# PortalsDualExpVCA.net
KiCad netlist of a schematic drawn in EAGLE
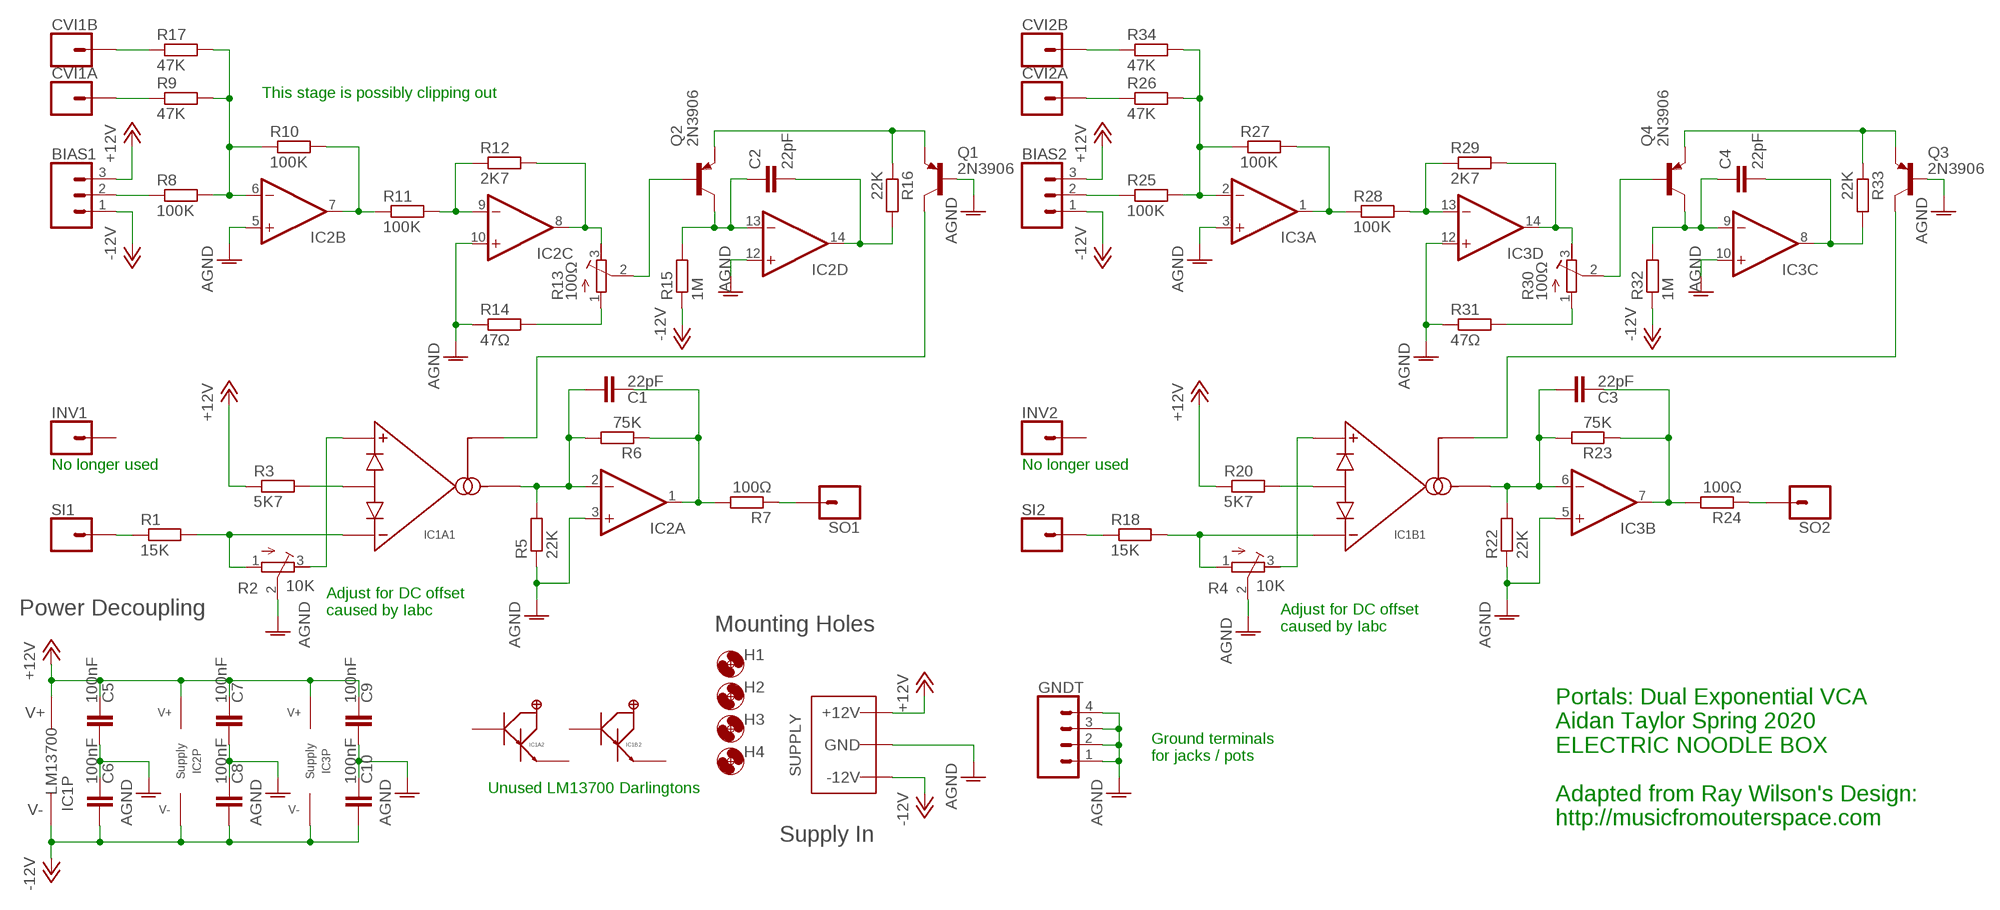
[diagram p0: schematic, sheet 1]

(export (version "E")
  (design (tool "Eeschema 10.0.6"))
  (components
    (comp (ref "BIAS1")
      (value "3XWIREPAD")
      (footprint "eagle-import:1X03")
      (libsource (lib "eagle-import") (part "3XWIREPAD"))
    )
    (comp (ref "BIAS2")
      (value "3XWIREPAD")
      (footprint "eagle-import:1X03")
      (libsource (lib "eagle-import") (part "3XWIREPAD"))
    )
    (comp (ref "C1")
      (value "22pF")
      (footprint "eagle-import:C050-025X075")
      (libsource (lib "eagle-import") (part "C-EU050-025X075"))
    )
    (comp (ref "C2")
      (value "22pF")
      (footprint "eagle-import:C050-025X075")
      (libsource (lib "eagle-import") (part "C-EU050-025X075"))
    )
    (comp (ref "C3")
      (value "22pF")
      (footprint "eagle-import:C050-025X075")
      (libsource (lib "eagle-import") (part "C-EU050-025X075"))
    )
    (comp (ref "C4")
      (value "22pF")
      (footprint "eagle-import:C050-025X075")
      (libsource (lib "eagle-import") (part "C-EU050-025X075"))
    )
    (comp (ref "C5")
      (value "100nF")
      (footprint "eagle-import:C050-025X075")
      (libsource (lib "eagle-import") (part "C-EU050-025X075"))
    )
    (comp (ref "C6")
      (value "100nF")
      (footprint "eagle-import:C050-025X075")
      (libsource (lib "eagle-import") (part "C-EU050-025X075"))
    )
    (comp (ref "C7")
      (value "100nF")
      (footprint "eagle-import:C050-025X075")
      (libsource (lib "eagle-import") (part "C-EU050-025X075"))
    )
    (comp (ref "C8")
      (value "100nF")
      (footprint "eagle-import:C050-025X075")
      (libsource (lib "eagle-import") (part "C-EU050-025X075"))
    )
    (comp (ref "C9")
      (value "100nF")
      (footprint "eagle-import:C050-025X075")
      (libsource (lib "eagle-import") (part "C-EU050-025X075"))
    )
    (comp (ref "C10")
      (value "100nF")
      (footprint "eagle-import:C050-025X075")
      (libsource (lib "eagle-import") (part "C-EU050-025X075"))
    )
    (comp (ref "CVI1A")
      (value "1XWIREPAD")
      (footprint "eagle-import:1X01")
      (libsource (lib "eagle-import") (part "1XWIREPAD"))
    )
    (comp (ref "CVI1B")
      (value "1XWIREPAD")
      (footprint "eagle-import:1X01")
      (libsource (lib "eagle-import") (part "1XWIREPAD"))
    )
    (comp (ref "CVI2A")
      (value "1XWIREPAD")
      (footprint "eagle-import:1X01")
      (libsource (lib "eagle-import") (part "1XWIREPAD"))
    )
    (comp (ref "CVI2B")
      (value "1XWIREPAD")
      (footprint "eagle-import:1X01")
      (libsource (lib "eagle-import") (part "1XWIREPAD"))
    )
    (comp (ref "GNDT")
      (value "4XWIREPAD")
      (footprint "eagle-import:1X04")
      (libsource (lib "eagle-import") (part "4XWIREPAD"))
    )
    (comp (ref "H1")
      (value "MOUNT-HOLE3.2")
      (footprint "eagle-import:3,2")
      (libsource (lib "eagle-import") (part "MOUNT-HOLE3.2"))
    )
    (comp (ref "H2")
      (value "MOUNT-HOLE3.2")
      (footprint "eagle-import:3,2")
      (libsource (lib "eagle-import") (part "MOUNT-HOLE3.2"))
    )
    (comp (ref "H3")
      (value "MOUNT-HOLE3.2")
      (footprint "eagle-import:3,2")
      (libsource (lib "eagle-import") (part "MOUNT-HOLE3.2"))
    )
    (comp (ref "H4")
      (value "MOUNT-HOLE3.2")
      (footprint "eagle-import:3,2")
      (libsource (lib "eagle-import") (part "MOUNT-HOLE3.2"))
    )
    (comp (ref "IC1")
      (value "LM13700DIL")
      (footprint "eagle-import:DIL16")
      (libsource (lib "eagle-import") (part "LM13700DIL"))
    )
    (comp (ref "IC2")
      (value "TL0X4DIL")
      (footprint "eagle-import:DIL14")
      (libsource (lib "eagle-import") (part "TL0X4DIL"))
    )
    (comp (ref "IC3")
      (value "TL0X4DIL")
      (footprint "eagle-import:DIL14")
      (libsource (lib "eagle-import") (part "TL0X4DIL"))
    )
    (comp (ref "INV1")
      (value "1XWIREPAD")
      (footprint "eagle-import:1X01")
      (libsource (lib "eagle-import") (part "1XWIREPAD"))
    )
    (comp (ref "INV2")
      (value "1XWIREPAD")
      (footprint "eagle-import:1X01")
      (libsource (lib "eagle-import") (part "1XWIREPAD"))
    )
    (comp (ref "Q1")
      (value "2N3906")
      (footprint "eagle-import:TO92")
      (libsource (lib "eagle-import") (part "2N3906"))
    )
    (comp (ref "Q2")
      (value "2N3906")
      (footprint "eagle-import:TO92")
      (libsource (lib "eagle-import") (part "2N3906"))
    )
    (comp (ref "Q3")
      (value "2N3906")
      (footprint "eagle-import:TO92")
      (libsource (lib "eagle-import") (part "2N3906"))
    )
    (comp (ref "Q4")
      (value "2N3906")
      (footprint "eagle-import:TO92")
      (libsource (lib "eagle-import") (part "2N3906"))
    )
    (comp (ref "R1")
      (value "15K")
      (footprint "eagle-import:0207_10")
      (libsource (lib "eagle-import") (part "R-EU_0207/10"))
    )
    (comp (ref "R2")
      (value "10K")
      (footprint "eagle-import:RTRIM3296W")
      (libsource (lib "eagle-import") (part "R-TRIMM3296W"))
    )
    (comp (ref "R3")
      (value "5K7")
      (footprint "eagle-import:0207_10")
      (libsource (lib "eagle-import") (part "R-EU_0207/10"))
    )
    (comp (ref "R4")
      (value "10K")
      (footprint "eagle-import:RTRIM3296W")
      (libsource (lib "eagle-import") (part "R-TRIMM3296W"))
    )
    (comp (ref "R5")
      (value "22K")
      (footprint "eagle-import:0207_10")
      (libsource (lib "eagle-import") (part "R-EU_0207/10"))
    )
    (comp (ref "R6")
      (value "75K")
      (footprint "eagle-import:0207_10")
      (libsource (lib "eagle-import") (part "R-EU_0207/10"))
    )
    (comp (ref "R7")
      (value "100Ω")
      (footprint "eagle-import:0207_10")
      (libsource (lib "eagle-import") (part "R-EU_0207/10"))
    )
    (comp (ref "R8")
      (value "100K")
      (footprint "eagle-import:0207_10")
      (libsource (lib "eagle-import") (part "R-EU_0207/10"))
    )
    (comp (ref "R9")
      (value "47K")
      (footprint "eagle-import:0207_10")
      (libsource (lib "eagle-import") (part "R-EU_0207/10"))
    )
    (comp (ref "R10")
      (value "100K")
      (footprint "eagle-import:0207_10")
      (libsource (lib "eagle-import") (part "R-EU_0207/10"))
    )
    (comp (ref "R11")
      (value "100K")
      (footprint "eagle-import:0207_10")
      (libsource (lib "eagle-import") (part "R-EU_0207/10"))
    )
    (comp (ref "R12")
      (value "2K7")
      (footprint "eagle-import:0207_10")
      (libsource (lib "eagle-import") (part "R-EU_0207/10"))
    )
    (comp (ref "R13")
      (value "100Ω")
      (footprint "eagle-import:RTRIM3296W")
      (libsource (lib "eagle-import") (part "R-TRIMM3296W"))
    )
    (comp (ref "R14")
      (value "47Ω")
      (footprint "eagle-import:0207_10")
      (libsource (lib "eagle-import") (part "R-EU_0207/10"))
    )
    (comp (ref "R15")
      (value "1M")
      (footprint "eagle-import:0207_10")
      (libsource (lib "eagle-import") (part "R-EU_0207/10"))
    )
    (comp (ref "R16")
      (value "22K")
      (footprint "eagle-import:0207_10")
      (libsource (lib "eagle-import") (part "R-EU_0207/10"))
    )
    (comp (ref "R17")
      (value "47K")
      (footprint "eagle-import:0207_10")
      (libsource (lib "eagle-import") (part "R-EU_0207/10"))
    )
    (comp (ref "R18")
      (value "15K")
      (footprint "eagle-import:0207_10")
      (libsource (lib "eagle-import") (part "R-EU_0207/10"))
    )
    (comp (ref "R20")
      (value "5K7")
      (footprint "eagle-import:0207_10")
      (libsource (lib "eagle-import") (part "R-EU_0207/10"))
    )
    (comp (ref "R22")
      (value "22K")
      (footprint "eagle-import:0207_10")
      (libsource (lib "eagle-import") (part "R-EU_0207/10"))
    )
    (comp (ref "R23")
      (value "75K")
      (footprint "eagle-import:0207_10")
      (libsource (lib "eagle-import") (part "R-EU_0207/10"))
    )
    (comp (ref "R24")
      (value "100Ω")
      (footprint "eagle-import:0207_10")
      (libsource (lib "eagle-import") (part "R-EU_0207/10"))
    )
    (comp (ref "R25")
      (value "100K")
      (footprint "eagle-import:0207_10")
      (libsource (lib "eagle-import") (part "R-EU_0207/10"))
    )
    (comp (ref "R26")
      (value "47K")
      (footprint "eagle-import:0207_10")
      (libsource (lib "eagle-import") (part "R-EU_0207/10"))
    )
    (comp (ref "R27")
      (value "100K")
      (footprint "eagle-import:0207_10")
      (libsource (lib "eagle-import") (part "R-EU_0207/10"))
    )
    (comp (ref "R28")
      (value "100K")
      (footprint "eagle-import:0207_10")
      (libsource (lib "eagle-import") (part "R-EU_0207/10"))
    )
    (comp (ref "R29")
      (value "2K7")
      (footprint "eagle-import:0207_10")
      (libsource (lib "eagle-import") (part "R-EU_0207/10"))
    )
    (comp (ref "R30")
      (value "100Ω")
      (footprint "eagle-import:RTRIM3296W")
      (libsource (lib "eagle-import") (part "R-TRIMM3296W"))
    )
    (comp (ref "R31")
      (value "47Ω")
      (footprint "eagle-import:0207_10")
      (libsource (lib "eagle-import") (part "R-EU_0207/10"))
    )
    (comp (ref "R32")
      (value "1M")
      (footprint "eagle-import:0207_10")
      (libsource (lib "eagle-import") (part "R-EU_0207/10"))
    )
    (comp (ref "R33")
      (value "22K")
      (footprint "eagle-import:0207_10")
      (libsource (lib "eagle-import") (part "R-EU_0207/10"))
    )
    (comp (ref "R34")
      (value "47K")
      (footprint "eagle-import:0207_10")
      (libsource (lib "eagle-import") (part "R-EU_0207/10"))
    )
    (comp (ref "SI1")
      (value "1XWIREPAD")
      (footprint "eagle-import:1X01")
      (libsource (lib "eagle-import") (part "1XWIREPAD"))
    )
    (comp (ref "SI2")
      (value "1XWIREPAD")
      (footprint "eagle-import:1X01")
      (libsource (lib "eagle-import") (part "1XWIREPAD"))
    )
    (comp (ref "SO1")
      (value "1XWIREPAD")
      (footprint "eagle-import:1X01")
      (libsource (lib "eagle-import") (part "1XWIREPAD"))
    )
    (comp (ref "SO2")
      (value "1XWIREPAD")
      (footprint "eagle-import:1X01")
      (libsource (lib "eagle-import") (part "1XWIREPAD"))
    )
    (comp (ref "WP1")
      (value "COMBO_SUPPLY_HEADER")
      (footprint "eagle-import:COMBINED_POWER")
      (libsource (lib "eagle-import") (part "COMBO_SUPPLY_HEADER"))
    )
  )
  (nets
    (net (code "1") (name "+12V") (class "Default")
      (node (ref "BIAS1") (pin "3") (pinfunction "3_3") (pintype "passive"))
      (node (ref "BIAS2") (pin "3") (pinfunction "3_3") (pintype "passive"))
      (node (ref "C5") (pin "2") (pinfunction "2_2") (pintype "passive"))
      (node (ref "C7") (pin "2") (pinfunction "2_2") (pintype "passive"))
      (node (ref "C9") (pin "2") (pinfunction "2_2") (pintype "passive"))
      (node (ref "IC1") (pin "11") (pinfunction "V+_11") (pintype "power_in"))
      (node (ref "IC2") (pin "4") (pinfunction "V+_4") (pintype "bidirectional"))
      (node (ref "IC3") (pin "4") (pinfunction "V+_4") (pintype "bidirectional"))
      (node (ref "R20") (pin "1") (pinfunction "1_1") (pintype "passive"))
      (node (ref "R3") (pin "1") (pinfunction "1_1") (pintype "passive"))
      (node (ref "WP1") (pin "V+1") (pinfunction "V++_V+1") (pintype "power_in"))
      (node (ref "WP1") (pin "V+2") (pinfunction "V++_V+2") (pintype "power_in"))
      (node (ref "WP1") (pin "V+3") (pinfunction "V++_V+3") (pintype "power_in"))
    )
    (net (code "2") (name "-12V") (class "Default")
      (node (ref "BIAS1") (pin "1") (pinfunction "1_1") (pintype "passive"))
      (node (ref "BIAS2") (pin "1") (pinfunction "1_1") (pintype "passive"))
      (node (ref "C10") (pin "1") (pinfunction "1_1") (pintype "passive"))
      (node (ref "C6") (pin "1") (pinfunction "1_1") (pintype "passive"))
      (node (ref "C8") (pin "1") (pinfunction "1_1") (pintype "passive"))
      (node (ref "IC1") (pin "6") (pinfunction "V-_6") (pintype "power_in"))
      (node (ref "IC2") (pin "11") (pinfunction "V-_11") (pintype "bidirectional"))
      (node (ref "IC3") (pin "11") (pinfunction "V-_11") (pintype "bidirectional"))
      (node (ref "R15") (pin "1") (pinfunction "1_1") (pintype "passive"))
      (node (ref "R32") (pin "1") (pinfunction "1_1") (pintype "passive"))
      (node (ref "WP1") (pin "V-1") (pinfunction "V--_V-1") (pintype "power_in"))
      (node (ref "WP1") (pin "V-2") (pinfunction "V--_V-2") (pintype "power_in"))
      (node (ref "WP1") (pin "V-3") (pinfunction "V--_V-3") (pintype "power_in"))
    )
    (net (code "3") (name "AGND") (class "Default")
      (node (ref "C10") (pin "2") (pinfunction "2_2") (pintype "passive"))
      (node (ref "C5") (pin "1") (pinfunction "1_1") (pintype "passive"))
      (node (ref "C6") (pin "2") (pinfunction "2_2") (pintype "passive"))
      (node (ref "C7") (pin "1") (pinfunction "1_1") (pintype "passive"))
      (node (ref "C8") (pin "2") (pinfunction "2_2") (pintype "passive"))
      (node (ref "C9") (pin "1") (pinfunction "1_1") (pintype "passive"))
      (node (ref "GNDT") (pin "1") (pinfunction "1_1") (pintype "passive"))
      (node (ref "GNDT") (pin "2") (pinfunction "2_2") (pintype "passive"))
      (node (ref "GNDT") (pin "3") (pinfunction "3_3") (pintype "passive"))
      (node (ref "GNDT") (pin "4") (pinfunction "4_4") (pintype "passive"))
      (node (ref "IC2") (pin "10") (pinfunction "+IN_10") (pintype "input"))
      (node (ref "IC2") (pin "12") (pinfunction "+IN_12") (pintype "input"))
      (node (ref "IC2") (pin "3") (pinfunction "+IN_3") (pintype "input"))
      (node (ref "IC2") (pin "5") (pinfunction "+IN_5") (pintype "input"))
      (node (ref "IC3") (pin "10") (pinfunction "+IN_10") (pintype "input"))
      (node (ref "IC3") (pin "12") (pinfunction "+IN_12") (pintype "input"))
      (node (ref "IC3") (pin "3") (pinfunction "+IN_3") (pintype "input"))
      (node (ref "IC3") (pin "5") (pinfunction "+IN_5") (pintype "input"))
      (node (ref "Q1") (pin "2") (pinfunction "B_2") (pintype "passive"))
      (node (ref "Q3") (pin "2") (pinfunction "B_2") (pintype "passive"))
      (node (ref "R14") (pin "1") (pinfunction "1_1") (pintype "passive"))
      (node (ref "R2") (pin "2") (pinfunction "S_2") (pintype "passive"))
      (node (ref "R22") (pin "1") (pinfunction "1_1") (pintype "passive"))
      (node (ref "R31") (pin "1") (pinfunction "1_1") (pintype "passive"))
      (node (ref "R4") (pin "2") (pinfunction "S_2") (pintype "passive"))
      (node (ref "R5") (pin "1") (pinfunction "1_1") (pintype "passive"))
      (node (ref "WP1") (pin "GND1") (pinfunction "AGND_GND1") (pintype "power_in"))
      (node (ref "WP1") (pin "GND2") (pinfunction "AGND_GND2") (pintype "power_in"))
      (node (ref "WP1") (pin "GND3") (pinfunction "AGND_GND3") (pintype "power_in"))
      (node (ref "WP1") (pin "GND4") (pinfunction "AGND_GND4") (pintype "power_in"))
      (node (ref "WP1") (pin "GND5") (pinfunction "AGND_GND5") (pintype "power_in"))
      (node (ref "WP1") (pin "GND6") (pinfunction "AGND_GND6") (pintype "power_in"))
      (node (ref "WP1") (pin "GND7") (pinfunction "AGND_GND7") (pintype "power_in"))
      (node (ref "WP1") (pin "GND8") (pinfunction "AGND_GND8") (pintype "power_in"))
    )
    (net (code "4") (name "Net-(BIAS1-Pad2)") (class "Default")
      (node (ref "BIAS1") (pin "2") (pinfunction "2_2") (pintype "passive"))
      (node (ref "R8") (pin "1") (pinfunction "1_1") (pintype "passive"))
    )
    (net (code "5") (name "Net-(BIAS2-Pad2)") (class "Default")
      (node (ref "BIAS2") (pin "2") (pinfunction "2_2") (pintype "passive"))
      (node (ref "R25") (pin "1") (pinfunction "1_1") (pintype "passive"))
    )
    (net (code "6") (name "Net-(CVI1A-Pad1)") (class "Default")
      (node (ref "CVI1A") (pin "1") (pinfunction "1_1") (pintype "passive"))
      (node (ref "R9") (pin "1") (pinfunction "1_1") (pintype "passive"))
    )
    (net (code "7") (name "Net-(CVI1B-Pad1)") (class "Default")
      (node (ref "CVI1B") (pin "1") (pinfunction "1_1") (pintype "passive"))
      (node (ref "R17") (pin "1") (pinfunction "1_1") (pintype "passive"))
    )
    (net (code "8") (name "Net-(CVI2A-Pad1)") (class "Default")
      (node (ref "CVI2A") (pin "1") (pinfunction "1_1") (pintype "passive"))
      (node (ref "R26") (pin "1") (pinfunction "1_1") (pintype "passive"))
    )
    (net (code "9") (name "Net-(CVI2B-Pad1)") (class "Default")
      (node (ref "CVI2B") (pin "1") (pinfunction "1_1") (pintype "passive"))
      (node (ref "R34") (pin "1") (pinfunction "1_1") (pintype "passive"))
    )
    (net (code "10") (name "Net-(IC1A-AMP+)") (class "Default")
      (node (ref "IC1") (pin "3") (pinfunction "AMP+_3") (pintype "input"))
      (node (ref "R2") (pin "3") (pinfunction "E_3") (pintype "passive"))
    )
    (net (code "11") (name "Net-(IC1A-AMP-)") (class "Default")
      (node (ref "IC1") (pin "4") (pinfunction "AMP-_4") (pintype "input"))
      (node (ref "R1") (pin "2") (pinfunction "2_2") (pintype "passive"))
      (node (ref "R2") (pin "1") (pinfunction "A_1") (pintype "passive"))
    )
    (net (code "12") (name "Net-(IC1A-AMPBIAS)") (class "Default")
      (node (ref "IC1") (pin "1") (pinfunction "AMPBIAS_1") (pintype "input"))
      (node (ref "Q1") (pin "1") (pinfunction "C_1") (pintype "passive"))
    )
    (net (code "13") (name "Net-(IC1A-AMPOUT)") (class "Default")
      (node (ref "C1") (pin "1") (pinfunction "1_1") (pintype "passive"))
      (node (ref "IC1") (pin "5") (pinfunction "AMPOUT_5") (pintype "output"))
      (node (ref "IC2") (pin "2") (pinfunction "-IN_2") (pintype "input"))
      (node (ref "R5") (pin "2") (pinfunction "2_2") (pintype "passive"))
      (node (ref "R6") (pin "2") (pinfunction "2_2") (pintype "passive"))
    )
    (net (code "14") (name "Net-(IC1A-DIODES)") (class "Default")
      (node (ref "IC1") (pin "2") (pinfunction "DIODES_2") (pintype "input"))
      (node (ref "R3") (pin "2") (pinfunction "2_2") (pintype "passive"))
    )
    (net (code "15") (name "Net-(IC1C-AMP+)") (class "Default")
      (node (ref "IC1") (pin "14") (pinfunction "AMP+_14") (pintype "input"))
      (node (ref "R4") (pin "3") (pinfunction "E_3") (pintype "passive"))
    )
    (net (code "16") (name "Net-(IC1C-AMP-)") (class "Default")
      (node (ref "IC1") (pin "13") (pinfunction "AMP-_13") (pintype "input"))
      (node (ref "R18") (pin "2") (pinfunction "2_2") (pintype "passive"))
      (node (ref "R4") (pin "1") (pinfunction "A_1") (pintype "passive"))
    )
    (net (code "17") (name "Net-(IC1C-AMPBIAS)") (class "Default")
      (node (ref "IC1") (pin "16") (pinfunction "AMPBIAS_16") (pintype "input"))
      (node (ref "Q3") (pin "1") (pinfunction "C_1") (pintype "passive"))
    )
    (net (code "18") (name "Net-(IC1C-AMPOUT)") (class "Default")
      (node (ref "C3") (pin "1") (pinfunction "1_1") (pintype "passive"))
      (node (ref "IC1") (pin "12") (pinfunction "AMPOUT_12") (pintype "output"))
      (node (ref "IC3") (pin "6") (pinfunction "-IN_6") (pintype "input"))
      (node (ref "R22") (pin "2") (pinfunction "2_2") (pintype "passive"))
      (node (ref "R23") (pin "2") (pinfunction "2_2") (pintype "passive"))
    )
    (net (code "19") (name "Net-(IC1C-DIODES)") (class "Default")
      (node (ref "IC1") (pin "15") (pinfunction "DIODES_15") (pintype "input"))
      (node (ref "R20") (pin "2") (pinfunction "2_2") (pintype "passive"))
    )
    (net (code "20") (name "Net-(IC2A-OUT)") (class "Default")
      (node (ref "C1") (pin "2") (pinfunction "2_2") (pintype "passive"))
      (node (ref "IC2") (pin "1") (pinfunction "OUT_1") (pintype "output"))
      (node (ref "R6") (pin "1") (pinfunction "1_1") (pintype "passive"))
      (node (ref "R7") (pin "2") (pinfunction "2_2") (pintype "passive"))
    )
    (net (code "21") (name "Net-(IC2B--IN)") (class "Default")
      (node (ref "IC2") (pin "6") (pinfunction "-IN_6") (pintype "input"))
      (node (ref "R10") (pin "1") (pinfunction "1_1") (pintype "passive"))
      (node (ref "R17") (pin "2") (pinfunction "2_2") (pintype "passive"))
      (node (ref "R8") (pin "2") (pinfunction "2_2") (pintype "passive"))
      (node (ref "R9") (pin "2") (pinfunction "2_2") (pintype "passive"))
    )
    (net (code "22") (name "Net-(IC2B-OUT)") (class "Default")
      (node (ref "IC2") (pin "7") (pinfunction "OUT_7") (pintype "output"))
      (node (ref "R10") (pin "2") (pinfunction "2_2") (pintype "passive"))
      (node (ref "R11") (pin "1") (pinfunction "1_1") (pintype "passive"))
    )
    (net (code "23") (name "Net-(IC2C--IN)") (class "Default")
      (node (ref "IC2") (pin "9") (pinfunction "-IN_9") (pintype "input"))
      (node (ref "R11") (pin "2") (pinfunction "2_2") (pintype "passive"))
      (node (ref "R12") (pin "1") (pinfunction "1_1") (pintype "passive"))
    )
    (net (code "24") (name "Net-(IC2C-OUT)") (class "Default")
      (node (ref "IC2") (pin "8") (pinfunction "OUT_8") (pintype "output"))
      (node (ref "R12") (pin "2") (pinfunction "2_2") (pintype "passive"))
      (node (ref "R13") (pin "3") (pinfunction "E_3") (pintype "passive"))
    )
    (net (code "25") (name "Net-(IC2D--IN)") (class "Default")
      (node (ref "C2") (pin "1") (pinfunction "1_1") (pintype "passive"))
      (node (ref "IC2") (pin "13") (pinfunction "-IN_13") (pintype "input"))
      (node (ref "Q2") (pin "1") (pinfunction "C_1") (pintype "passive"))
      (node (ref "R15") (pin "2") (pinfunction "2_2") (pintype "passive"))
    )
    (net (code "26") (name "Net-(IC2D-OUT)") (class "Default")
      (node (ref "C2") (pin "2") (pinfunction "2_2") (pintype "passive"))
      (node (ref "IC2") (pin "14") (pinfunction "OUT_14") (pintype "output"))
      (node (ref "R16") (pin "2") (pinfunction "2_2") (pintype "passive"))
    )
    (net (code "27") (name "Net-(IC3A--IN)") (class "Default")
      (node (ref "IC3") (pin "2") (pinfunction "-IN_2") (pintype "input"))
      (node (ref "R25") (pin "2") (pinfunction "2_2") (pintype "passive"))
      (node (ref "R26") (pin "2") (pinfunction "2_2") (pintype "passive"))
      (node (ref "R27") (pin "1") (pinfunction "1_1") (pintype "passive"))
      (node (ref "R34") (pin "2") (pinfunction "2_2") (pintype "passive"))
    )
    (net (code "28") (name "Net-(IC3A-OUT)") (class "Default")
      (node (ref "IC3") (pin "1") (pinfunction "OUT_1") (pintype "output"))
      (node (ref "R27") (pin "2") (pinfunction "2_2") (pintype "passive"))
      (node (ref "R28") (pin "1") (pinfunction "1_1") (pintype "passive"))
    )
    (net (code "29") (name "Net-(IC3B-OUT)") (class "Default")
      (node (ref "C3") (pin "2") (pinfunction "2_2") (pintype "passive"))
      (node (ref "IC3") (pin "7") (pinfunction "OUT_7") (pintype "output"))
      (node (ref "R23") (pin "1") (pinfunction "1_1") (pintype "passive"))
      (node (ref "R24") (pin "2") (pinfunction "2_2") (pintype "passive"))
    )
    (net (code "30") (name "Net-(IC3C--IN)") (class "Default")
      (node (ref "C4") (pin "1") (pinfunction "1_1") (pintype "passive"))
      (node (ref "IC3") (pin "9") (pinfunction "-IN_9") (pintype "input"))
      (node (ref "Q4") (pin "1") (pinfunction "C_1") (pintype "passive"))
      (node (ref "R32") (pin "2") (pinfunction "2_2") (pintype "passive"))
    )
    (net (code "31") (name "Net-(IC3C-OUT)") (class "Default")
      (node (ref "C4") (pin "2") (pinfunction "2_2") (pintype "passive"))
      (node (ref "IC3") (pin "8") (pinfunction "OUT_8") (pintype "output"))
      (node (ref "R33") (pin "2") (pinfunction "2_2") (pintype "passive"))
    )
    (net (code "32") (name "Net-(IC3D--IN)") (class "Default")
      (node (ref "IC3") (pin "13") (pinfunction "-IN_13") (pintype "input"))
      (node (ref "R28") (pin "2") (pinfunction "2_2") (pintype "passive"))
      (node (ref "R29") (pin "1") (pinfunction "1_1") (pintype "passive"))
    )
    (net (code "33") (name "Net-(IC3D-OUT)") (class "Default")
      (node (ref "IC3") (pin "14") (pinfunction "OUT_14") (pintype "output"))
      (node (ref "R29") (pin "2") (pinfunction "2_2") (pintype "passive"))
      (node (ref "R30") (pin "3") (pinfunction "E_3") (pintype "passive"))
    )
    (net (code "34") (name "Net-(Q1-E)") (class "Default")
      (node (ref "Q1") (pin "3") (pinfunction "E_3") (pintype "passive"))
      (node (ref "Q2") (pin "3") (pinfunction "E_3") (pintype "passive"))
      (node (ref "R16") (pin "1") (pinfunction "1_1") (pintype "passive"))
    )
    (net (code "35") (name "Net-(Q2-B)") (class "Default")
      (node (ref "Q2") (pin "2") (pinfunction "B_2") (pintype "passive"))
      (node (ref "R13") (pin "2") (pinfunction "S_2") (pintype "passive"))
    )
    (net (code "36") (name "Net-(Q3-E)") (class "Default")
      (node (ref "Q3") (pin "3") (pinfunction "E_3") (pintype "passive"))
      (node (ref "Q4") (pin "3") (pinfunction "E_3") (pintype "passive"))
      (node (ref "R33") (pin "1") (pinfunction "1_1") (pintype "passive"))
    )
    (net (code "37") (name "Net-(Q4-B)") (class "Default")
      (node (ref "Q4") (pin "2") (pinfunction "B_2") (pintype "passive"))
      (node (ref "R30") (pin "2") (pinfunction "S_2") (pintype "passive"))
    )
    (net (code "38") (name "Net-(R1-Pad1)") (class "Default")
      (node (ref "R1") (pin "1") (pinfunction "1_1") (pintype "passive"))
      (node (ref "SI1") (pin "1") (pinfunction "1_1") (pintype "passive"))
    )
    (net (code "39") (name "Net-(R7-Pad1)") (class "Default")
      (node (ref "R7") (pin "1") (pinfunction "1_1") (pintype "passive"))
      (node (ref "SO1") (pin "1") (pinfunction "1_1") (pintype "passive"))
    )
    (net (code "40") (name "Net-(R13-A)") (class "Default")
      (node (ref "R13") (pin "1") (pinfunction "A_1") (pintype "passive"))
      (node (ref "R14") (pin "2") (pinfunction "2_2") (pintype "passive"))
    )
    (net (code "41") (name "Net-(R18-Pad1)") (class "Default")
      (node (ref "R18") (pin "1") (pinfunction "1_1") (pintype "passive"))
      (node (ref "SI2") (pin "1") (pinfunction "1_1") (pintype "passive"))
    )
    (net (code "42") (name "Net-(R24-Pad1)") (class "Default")
      (node (ref "R24") (pin "1") (pinfunction "1_1") (pintype "passive"))
      (node (ref "SO2") (pin "1") (pinfunction "1_1") (pintype "passive"))
    )
    (net (code "43") (name "Net-(R30-A)") (class "Default")
      (node (ref "R30") (pin "1") (pinfunction "A_1") (pintype "passive"))
      (node (ref "R31") (pin "2") (pinfunction "2_2") (pintype "passive"))
    )
    (net (code "44") (name "unconnected-(IC1B-BUFF_IN-Pad7)") (class "Default")
      (node (ref "IC1") (pin "7") (pinfunction "BUFF_IN_7") (pintype "input"))
    )
    (net (code "45") (name "unconnected-(IC1B-BUFF_OUT-Pad8)") (class "Default")
      (node (ref "IC1") (pin "8") (pinfunction "BUFF_OUT_8") (pintype "bidirectional"))
    )
    (net (code "46") (name "unconnected-(IC1D-BUFF_IN-Pad10)") (class "Default")
      (node (ref "IC1") (pin "10") (pinfunction "BUFF_IN_10") (pintype "input"))
    )
    (net (code "47") (name "unconnected-(IC1D-BUFF_OUT-Pad9)") (class "Default")
      (node (ref "IC1") (pin "9") (pinfunction "BUFF_OUT_9") (pintype "bidirectional"))
    )
    (net (code "48") (name "unconnected-(INV1-Pad1)") (class "Default")
      (node (ref "INV1") (pin "1") (pinfunction "1_1") (pintype "passive"))
    )
    (net (code "49") (name "unconnected-(INV2-Pad1)") (class "Default")
      (node (ref "INV2") (pin "1") (pinfunction "1_1") (pintype "passive"))
    )
  )
)
